# MCU.net
KiCad netlist of a schematic drawn in EasyEDA Pro
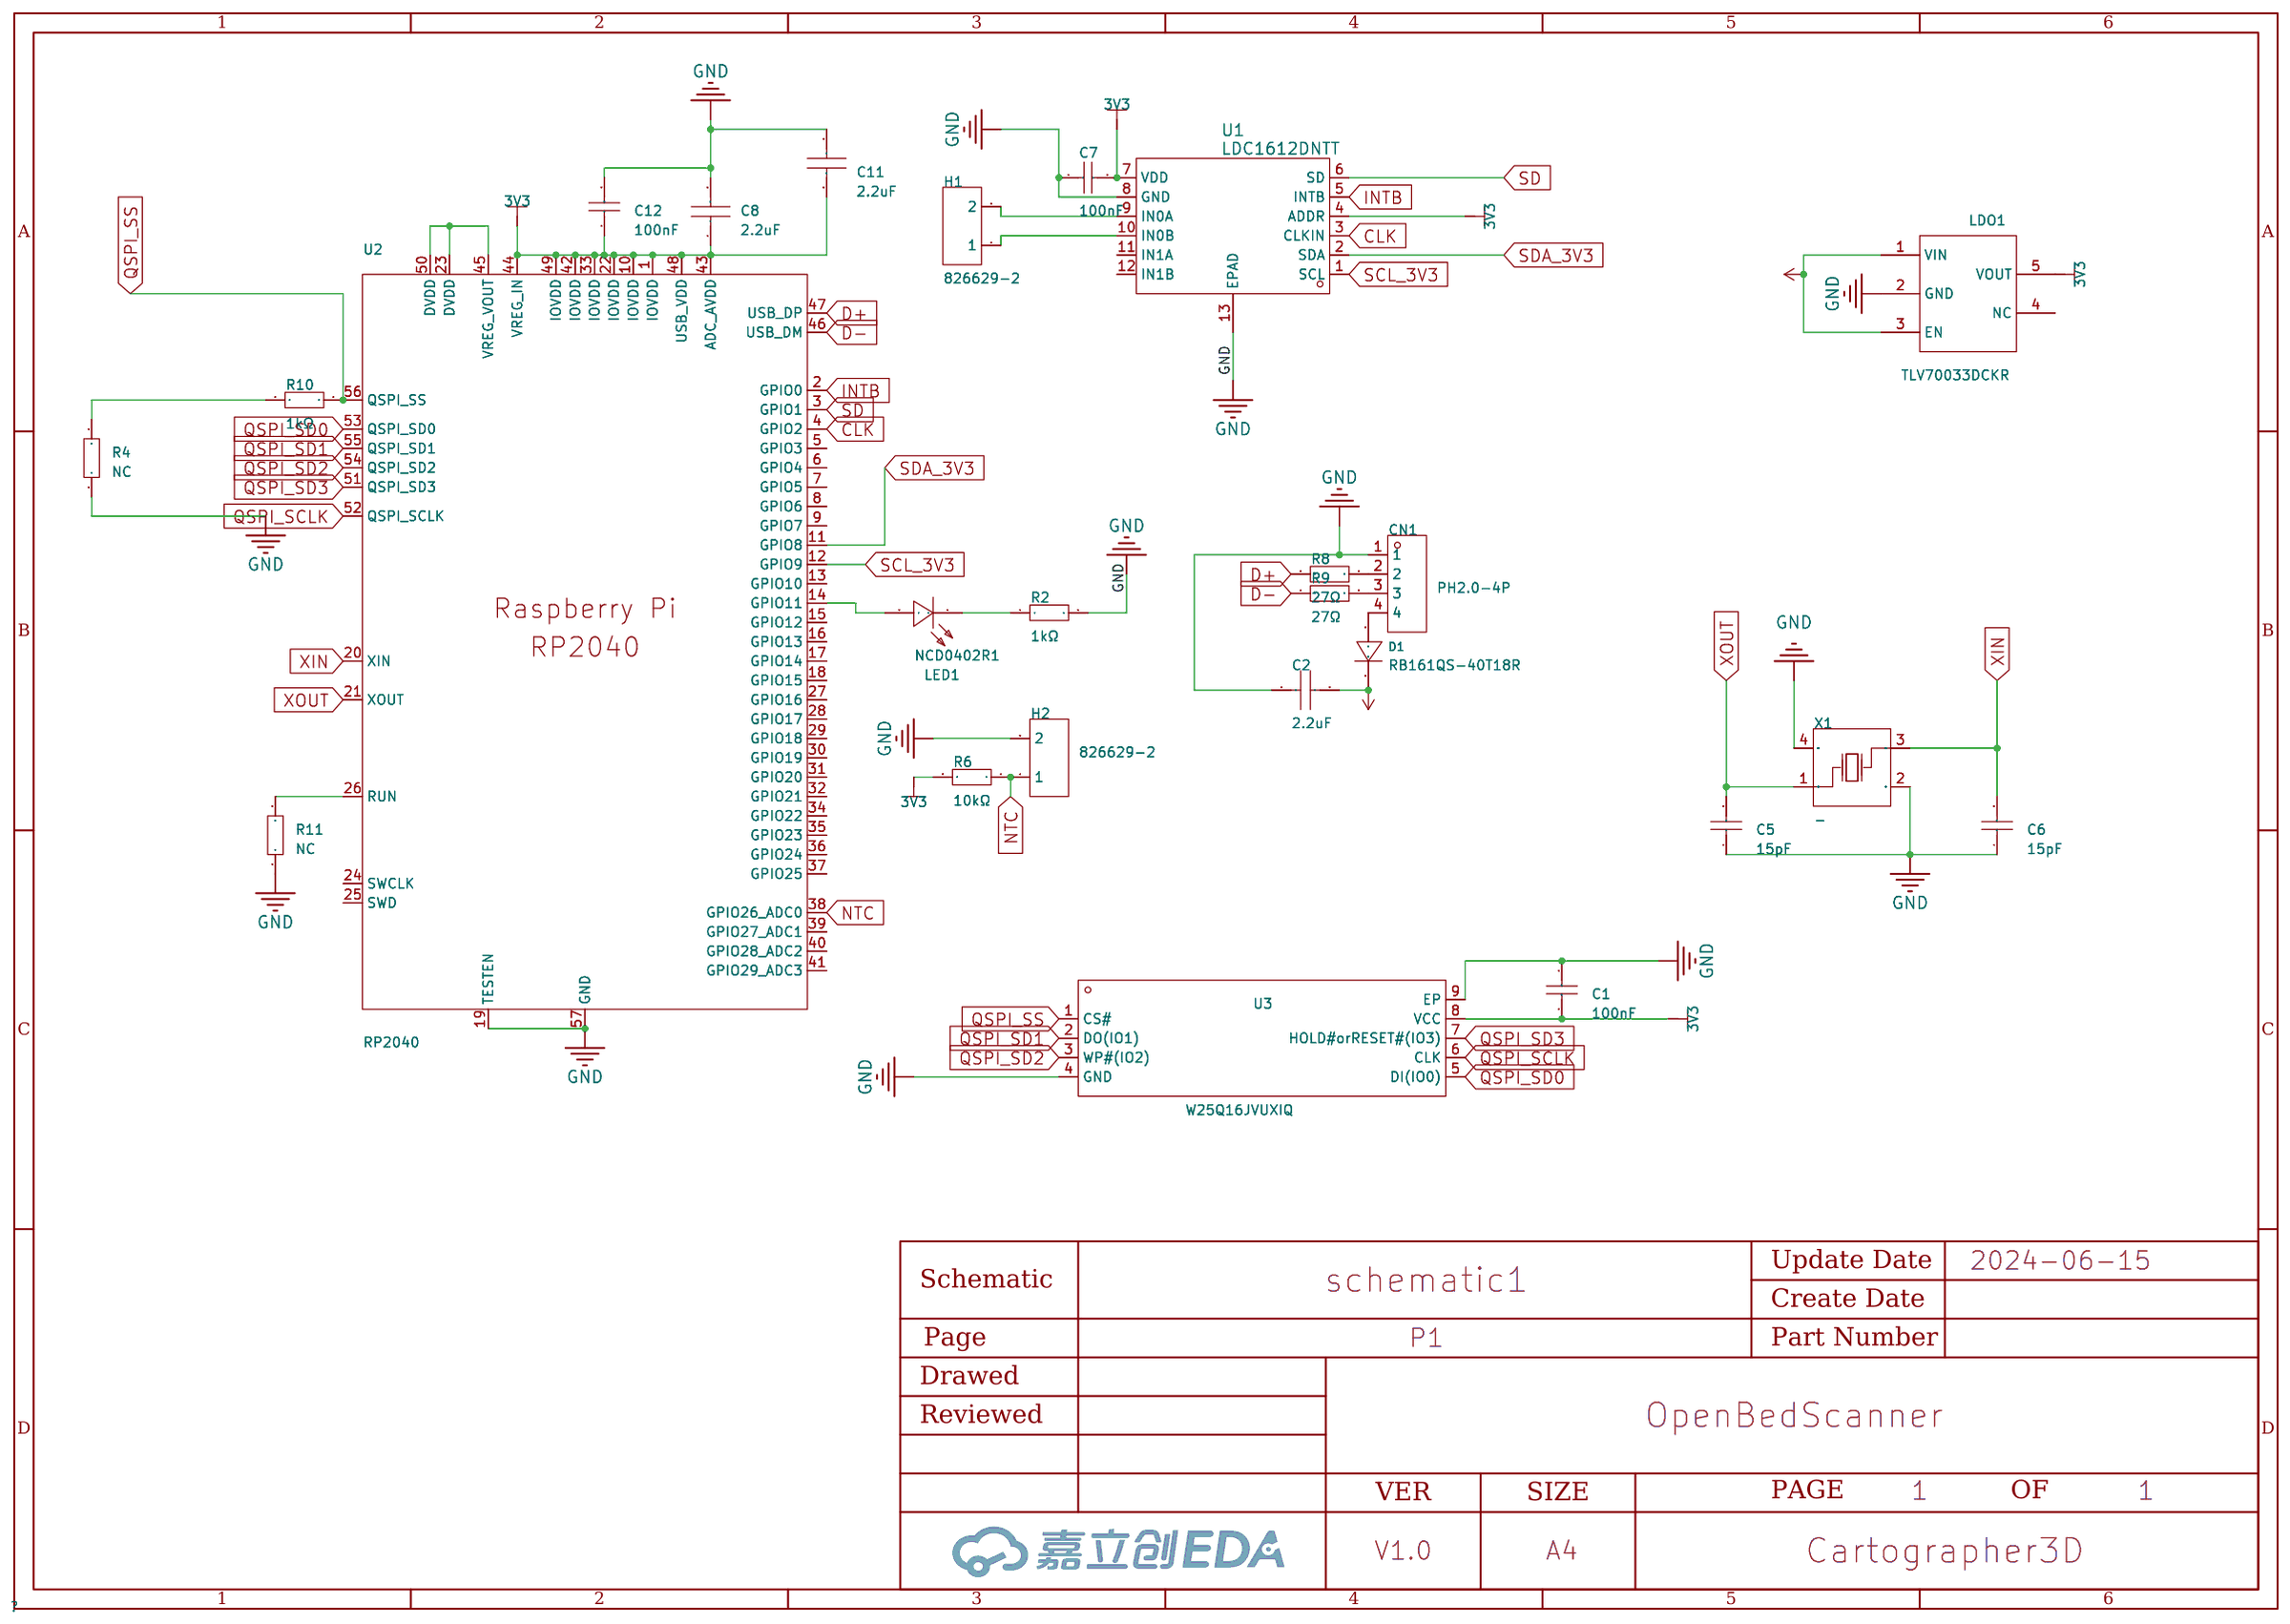
[diagram p0: schematic sheet]

(export (version "E")
  (design (tool "Eeschema 10.0.6"))
  (components
    (comp (ref "C1")
      (value "100nF")
      (footprint "easyedapro:C0402")
      (description "容值:100nF;精度:±10%;额定电压:16V;材质(温度系数):X7R;")
      (fields (field (name "Manufacturer Part") "0402B104K160NT") (field (name "Manufacturer") "FH(风华)"))
      (libsource (lib "easyedapro") (part "0402B104K160NT"))
    )
    (comp (ref "C2")
      (value "2.2uF")
      (footprint "easyedapro:C0402")
      (description "容值:2.2uF;精度:±20%;额定电压:6.3V;材质(温度系数):X5R;")
      (fields
        (field (name "Manufacturer Part") "CL05A225MQ5NSNC")
        (field (name "Manufacturer") "SAMSUNG(三星)")
      )
      (libsource (lib "easyedapro") (part "CL05A225MQ5NSNC"))
    )
    (comp (ref "C5")
      (value "15pF")
      (footprint "easyedapro:C0402")
      (description "容值:15pF;精度:±5%;额定电压:50V;材质(温度系数):C0G;")
      (fields (field (name "Manufacturer Part") "0402CG150J500NT") (field (name "Manufacturer") "FH(风华)"))
      (libsource (lib "easyedapro") (part "0402CG150J500NT"))
    )
    (comp (ref "C6")
      (value "15pF")
      (footprint "easyedapro:C0402")
      (description "容值:15pF;精度:±5%;额定电压:50V;材质(温度系数):C0G;")
      (fields (field (name "Manufacturer Part") "0402CG150J500NT") (field (name "Manufacturer") "FH(风华)"))
      (libsource (lib "easyedapro") (part "0402CG150J500NT"))
    )
    (comp (ref "C7")
      (value "100nF")
      (footprint "easyedapro:C0603")
      (description "容值:100nF;精度:±10%;额定电压:50V;材质(温度系数):X7R;")
      (fields (field (name "Manufacturer Part") "0402B104K160NT") (field (name "Manufacturer") "FH(风华)"))
      (libsource (lib "easyedapro") (part "0603B104K500NT"))
    )
    (comp (ref "C8")
      (value "2.2uF")
      (footprint "easyedapro:C0402")
      (description "容值:2.2uF;精度:±20%;额定电压:6.3V;材质(温度系数):X5R;")
      (fields
        (field (name "Manufacturer Part") "CL05A225MQ5NSNC")
        (field (name "Manufacturer") "SAMSUNG(三星)")
      )
      (libsource (lib "easyedapro") (part "CL05A225MQ5NSNC"))
    )
    (comp (ref "C11")
      (value "2.2uF")
      (footprint "easyedapro:C0402")
      (description "容值:2.2uF;精度:±20%;额定电压:6.3V;材质(温度系数):X5R;")
      (fields
        (field (name "Manufacturer Part") "CL05A225MQ5NSNC")
        (field (name "Manufacturer") "SAMSUNG(三星)")
      )
      (libsource (lib "easyedapro") (part "CL05A225MQ5NSNC"))
    )
    (comp (ref "C12")
      (value "100nF")
      (footprint "easyedapro:C0603")
      (description "容值:100nF;精度:±10%;额定电压:50V;材质(温度系数):X7R;")
      (fields (field (name "Manufacturer Part") "0402B104K160NT") (field (name "Manufacturer") "FH(风华)"))
      (libsource (lib "easyedapro") (part "0603B104K500NT"))
    )
    (comp (ref "CN1")
      (value "PH2.0-4P")
      (footprint "easyedapro:CONN-TH_PH2.0-4P")
      (fields (field (name "Manufacturer") "CAX(创都)"))
      (libsource (lib "easyedapro") (part "PH2.0-4P"))
    )
    (comp (ref "D1")
      (value "RB161QS-40T18R")
      (footprint "easyedapro:X2-DFN1006-2_L1.0-W0.6-P0.65-RD")
      (fields (field (name "Manufacturer") "ROHM(罗姆)"))
      (libsource (lib "easyedapro") (part "RB161QS-40T18R"))
    )
    (comp (ref "H1")
      (value "826629-2")
      (footprint "easyedapro:HDR-TH_2P-P2.54-V-M-1")
      (fields (field (name "Manufacturer") "TE Connectivity(美国泰科)"))
      (libsource (lib "easyedapro") (part "Header-Male-2.54_1x2"))
    )
    (comp (ref "H2")
      (value "826629-2")
      (footprint "easyedapro:HDR-TH_2P-P2.54-V-M-1")
      (fields (field (name "Manufacturer") "TE Connectivity(美国泰科)"))
      (libsource (lib "easyedapro") (part "Header-Male-2.54_1x2"))
    )
    (comp (ref "LDO1")
      (value "TLV70033DCKR")
      (footprint "easyedapro:SOT-23-5_L3.0-W1.7-P0.95-LS2.8-BL")
      (description "输出类型:固定;输出极性:正;最大输入电压:5.5V;输出电压:3.3V;输出电流:500mA;电源纹波抑制比(PSRR):50dB@(10kHz);")
      (fields (field (name "Manufacturer") "TI(德州仪器)"))
      (libsource (lib "easyedapro") (part "RT9013-33GB"))
    )
    (comp (ref "LED1")
      (value "NCD0402R1")
      (footprint "easyedapro:LED0402-RD")
      (description "发光颜色:红灯;")
      (fields (field (name "Manufacturer") "国星光电"))
      (libsource (lib "easyedapro") (part "FC-F1005HRK-620H5"))
    )
    (comp (ref "R2")
      (value "1kΩ")
      (footprint "easyedapro:R0402")
      (description "电阻类型:厚膜电阻;阻值:10kΩ;精度:±1%;功率:62.5mW;")
      (fields
        (field (name "Manufacturer Part") "0402WGF1001TCE")
        (field (name "Manufacturer") "UNI-ROYAL(厚声)")
      )
      (libsource (lib "easyedapro") (part "0402WGF1002TCE"))
    )
    (comp (ref "R4")
      (value "NC")
      (footprint "easyedapro:R0805")
      (description "电阻类型:厚膜电阻;阻值:10kΩ;精度:±1%;功率:125mW;")
      (fields
        (field (name "Manufacturer Part") "0805W8F1002T5E")
        (field (name "Manufacturer") "UNI-ROYAL(厚声)")
      )
      (libsource (lib "easyedapro") (part "0805W8F1002T5E"))
    )
    (comp (ref "R6")
      (value "10kΩ")
      (footprint "easyedapro:R0402")
      (description "电阻类型:厚膜电阻;阻值:1kΩ;精度:±1%;功率:62.5mW;")
      (fields
        (field (name "Manufacturer Part") "0402WGF1002TCE")
        (field (name "Manufacturer") "UNI-ROYAL(厚声)")
      )
      (libsource (lib "easyedapro") (part "0402WGF1001TCE"))
    )
    (comp (ref "R8")
      (value "27Ω")
      (footprint "easyedapro:R0402")
      (description "电阻类型:厚膜电阻;阻值:27Ω;精度:±1%;功率:62.5mW;")
      (fields
        (field (name "Manufacturer Part") "0402WGF270JTCE")
        (field (name "Manufacturer") "UNI-ROYAL(厚声)")
      )
      (libsource (lib "easyedapro") (part "0402WGF270JTCE"))
    )
    (comp (ref "R9")
      (value "27Ω")
      (footprint "easyedapro:R0402")
      (description "电阻类型:厚膜电阻;阻值:27Ω;精度:±1%;功率:62.5mW;")
      (fields
        (field (name "Manufacturer Part") "0402WGF270JTCE")
        (field (name "Manufacturer") "UNI-ROYAL(厚声)")
      )
      (libsource (lib "easyedapro") (part "0402WGF270JTCE"))
    )
    (comp (ref "R10")
      (value "1kΩ")
      (footprint "easyedapro:R0402")
      (description "电阻类型:厚膜电阻;阻值:10kΩ;精度:±1%;功率:62.5mW;")
      (fields
        (field (name "Manufacturer Part") "0402WGF1001TCE")
        (field (name "Manufacturer") "UNI-ROYAL(厚声)")
      )
      (libsource (lib "easyedapro") (part "0402WGF1002TCE"))
    )
    (comp (ref "R11")
      (value "NC")
      (footprint "easyedapro:R0805")
      (description "电阻类型:厚膜电阻;阻值:10kΩ;精度:±1%;功率:125mW;")
      (fields
        (field (name "Manufacturer Part") "0805W8F1002T5E")
        (field (name "Manufacturer") "UNI-ROYAL(厚声)")
      )
      (libsource (lib "easyedapro") (part "0805W8F1002T5E"))
    )
    (comp (ref "U1")
      (value "LDC1612DNTT")
      (footprint "easyedapro:WSON-12_L4.0-W4.0-P0.50-BL-EP")
      (fields (field (name "Manufacturer") "TI(德州仪器)"))
      (libsource (lib "easyedapro") (part "LDC1612DNTT"))
    )
    (comp (ref "U2")
      (value "RP2040")
      (footprint "easyedapro:LQFN-56_L7.0-W7.0-P0.4-EP")
      (description "应用领域:-;CPU内核:ARM-M系列;CPU最大主频:133MHz;工作电压范围:-;程序存储容量:-;程序存储器类型:-;RAM总容量:264KB;GPIO端口数量:30;")
      (fields (field (name "Manufacturer") "Raspberry Pi(树莓派)"))
      (libsource (lib "easyedapro") (part "RP2040"))
    )
    (comp (ref "U3")
      (value "W25Q16JVUXIQ")
      (footprint "easyedapro:USON-8_L3.0-W2.0-P0.50-BL-EP")
      (description "128Mbit(16MBx8bit),高速版,133MHz(266/532MHz Dual/Quad-SPI,66MB/S),比W25Q128FVSIG,W25Q128FVFIG更高速")
      (fields (field (name "Manufacturer") "WINBOND(华邦)"))
      (libsource (lib "easyedapro") (part "W25Q16JVUXIQ"))
    )
    (comp (ref "X1")
      (value "-")
      (footprint "easyedapro:OSC-SMD_4P-L3.2-W2.5-BL")
      (description "频率:12MHz;频率公差:±10ppm;负载电容:9pF;")
      (fields
        (field (name "Manufacturer Part") "XYDBPCNANF-12MHZ")
        (field (name "Manufacturer") "TAITIEN(泰艺电子)")
      )
      (libsource (lib "easyedapro") (part "X322512MLB4SI"))
    )
  )
  (nets
    (net (code "1") (name "3V3") (class "Default")
      (node (ref "C1") (pin "1") (pinfunction "1_1") (pintype "input"))
      (node (ref "C11") (pin "2") (pinfunction "2_2") (pintype "input"))
      (node (ref "C12") (pin "1") (pinfunction "1_1") (pintype "input"))
      (node (ref "C7") (pin "2") (pinfunction "2_2") (pintype "input"))
      (node (ref "C8") (pin "1") (pinfunction "1_1") (pintype "input"))
      (node (ref "LDO1") (pin "5") (pinfunction "VOUT_5") (pintype "input"))
      (node (ref "R6") (pin "2") (pinfunction "2_2") (pintype "input"))
      (node (ref "U1") (pin "4") (pinfunction "ADDR_4") (pintype "input"))
      (node (ref "U1") (pin "7") (pinfunction "VDD_7") (pintype "input"))
      (node (ref "U2") (pin "1") (pinfunction "IOVDD_1") (pintype "bidirectional"))
      (node (ref "U2") (pin "10") (pinfunction "IOVDD_10") (pintype "bidirectional"))
      (node (ref "U2") (pin "22") (pinfunction "IOVDD_22") (pintype "bidirectional"))
      (node (ref "U2") (pin "33") (pinfunction "IOVDD_33") (pintype "bidirectional"))
      (node (ref "U2") (pin "42") (pinfunction "IOVDD_42") (pintype "bidirectional"))
      (node (ref "U2") (pin "43") (pinfunction "ADC_AVDD_43") (pintype "bidirectional"))
      (node (ref "U2") (pin "44") (pinfunction "VREG_IN_44") (pintype "bidirectional"))
      (node (ref "U2") (pin "48") (pinfunction "USB_VDD_48") (pintype "bidirectional"))
      (node (ref "U2") (pin "49") (pinfunction "IOVDD_49") (pintype "bidirectional"))
      (node (ref "U3") (pin "8") (pinfunction "VCC_8") (pintype "input"))
    )
    (net (code "2") (name "5V") (class "Default")
      (node (ref "C2") (pin "2") (pinfunction "2_2") (pintype "input"))
      (node (ref "D1") (pin "1") (pinfunction "C_1") (pintype "input"))
      (node (ref "LDO1") (pin "1") (pinfunction "VIN_1") (pintype "input"))
      (node (ref "LDO1") (pin "3") (pinfunction "EN_3") (pintype "input"))
    )
    (net (code "3") (name "CLK") (class "Default")
      (node (ref "U1") (pin "3") (pinfunction "CLKIN_3") (pintype "input"))
      (node (ref "U2") (pin "4") (pinfunction "GPIO2_4") (pintype "bidirectional"))
    )
    (net (code "4") (name "D+") (class "Default")
      (node (ref "R8") (pin "1") (pinfunction "1_1") (pintype "input"))
      (node (ref "U2") (pin "47") (pinfunction "USB_DP_47") (pintype "bidirectional"))
    )
    (net (code "5") (name "D-") (class "Default")
      (node (ref "R9") (pin "1") (pinfunction "1_1") (pintype "input"))
      (node (ref "U2") (pin "46") (pinfunction "USB_DM_46") (pintype "bidirectional"))
    )
    (net (code "6") (name "GND") (class "Default")
      (node (ref "C1") (pin "2") (pinfunction "2_2") (pintype "input"))
      (node (ref "C11") (pin "1") (pinfunction "1_1") (pintype "input"))
      (node (ref "C12") (pin "2") (pinfunction "2_2") (pintype "input"))
      (node (ref "C2") (pin "1") (pinfunction "1_1") (pintype "input"))
      (node (ref "C5") (pin "1") (pinfunction "1_1") (pintype "input"))
      (node (ref "C6") (pin "1") (pinfunction "1_1") (pintype "input"))
      (node (ref "C7") (pin "1") (pinfunction "1_1") (pintype "input"))
      (node (ref "C8") (pin "2") (pinfunction "2_2") (pintype "input"))
      (node (ref "CN1") (pin "1") (pinfunction "1_1") (pintype "input"))
      (node (ref "H2") (pin "2") (pinfunction "2_2") (pintype "input"))
      (node (ref "LDO1") (pin "2") (pinfunction "GND_2") (pintype "input"))
      (node (ref "R11") (pin "1") (pinfunction "1_1") (pintype "input"))
      (node (ref "R2") (pin "2") (pinfunction "2_2") (pintype "input"))
      (node (ref "R4") (pin "2") (pinfunction "2_2") (pintype "input"))
      (node (ref "U1") (pin "13") (pinfunction "EPAD_13") (pintype "input"))
      (node (ref "U1") (pin "8") (pinfunction "GND_8") (pintype "input"))
      (node (ref "U2") (pin "19") (pinfunction "TESTEN_19") (pintype "input"))
      (node (ref "U2") (pin "57") (pinfunction "GND_57") (pintype "bidirectional"))
      (node (ref "U3") (pin "4") (pinfunction "GND_4") (pintype "input"))
      (node (ref "U3") (pin "9") (pinfunction "EP_9") (pintype "input"))
      (node (ref "X1") (pin "2") (pinfunction "GND_2") (pintype "input"))
      (node (ref "X1") (pin "4") (pinfunction "GND_4") (pintype "input"))
    )
    (net (code "7") (name "INTB") (class "Default")
      (node (ref "U1") (pin "5") (pinfunction "INTB_5") (pintype "input"))
      (node (ref "U2") (pin "2") (pinfunction "GPIO0_2") (pintype "bidirectional"))
    )
    (net (code "8") (name "NTC") (class "Default")
      (node (ref "H2") (pin "1") (pinfunction "1_1") (pintype "input"))
      (node (ref "R6") (pin "1") (pinfunction "1_1") (pintype "input"))
      (node (ref "U2") (pin "38") (pinfunction "GPIO26_ADC0_38") (pintype "bidirectional"))
    )
    (net (code "9") (name "Net-(CN1-Pad2)") (class "Default")
      (node (ref "CN1") (pin "2") (pinfunction "2_2") (pintype "input"))
      (node (ref "R8") (pin "2") (pinfunction "2_2") (pintype "input"))
    )
    (net (code "10") (name "Net-(CN1-Pad3)") (class "Default")
      (node (ref "CN1") (pin "3") (pinfunction "3_3") (pintype "input"))
      (node (ref "R9") (pin "2") (pinfunction "2_2") (pintype "input"))
    )
    (net (code "11") (name "Net-(D1-A)") (class "Default")
      (node (ref "CN1") (pin "4") (pinfunction "4_4") (pintype "input"))
      (node (ref "D1") (pin "2") (pinfunction "A_2") (pintype "input"))
    )
    (net (code "12") (name "Net-(LED1-A)") (class "Default")
      (node (ref "LED1") (pin "2") (pinfunction "A_2") (pintype "input"))
      (node (ref "U2") (pin "14") (pinfunction "GPIO11_14") (pintype "bidirectional"))
    )
    (net (code "13") (name "Net-(LED1-K)") (class "Default")
      (node (ref "LED1") (pin "1") (pinfunction "K_1") (pintype "input"))
      (node (ref "R2") (pin "1") (pinfunction "1_1") (pintype "input"))
    )
    (net (code "14") (name "Net-(R10-Pad2)") (class "Default")
      (node (ref "R10") (pin "2") (pinfunction "2_2") (pintype "input"))
      (node (ref "R4") (pin "1") (pinfunction "1_1") (pintype "input"))
    )
    (net (code "15") (name "Net-(U1-IN0A)") (class "Default")
      (node (ref "H1") (pin "2") (pinfunction "2_2") (pintype "input"))
      (node (ref "U1") (pin "9") (pinfunction "IN0A_9") (pintype "input"))
    )
    (net (code "16") (name "Net-(U1-IN0B)") (class "Default")
      (node (ref "H1") (pin "1") (pinfunction "1_1") (pintype "input"))
      (node (ref "U1") (pin "10") (pinfunction "IN0B_10") (pintype "input"))
    )
    (net (code "17") (name "Net-(U2-RUN)") (class "Default")
      (node (ref "R11") (pin "2") (pinfunction "2_2") (pintype "input"))
      (node (ref "U2") (pin "26") (pinfunction "RUN_26") (pintype "input"))
    )
    (net (code "18") (name "Net-(U2-VREG_VOUT)") (class "Default")
      (node (ref "U2") (pin "23") (pinfunction "DVDD_23") (pintype "bidirectional"))
      (node (ref "U2") (pin "45") (pinfunction "VREG_VOUT_45") (pintype "bidirectional"))
      (node (ref "U2") (pin "50") (pinfunction "DVDD_50") (pintype "bidirectional"))
    )
    (net (code "19") (name "QSPI_SCLK") (class "Default")
      (node (ref "U2") (pin "52") (pinfunction "QSPI_SCLK_52") (pintype "output"))
      (node (ref "U3") (pin "6") (pinfunction "CLK_6") (pintype "input"))
    )
    (net (code "20") (name "QSPI_SD0") (class "Default")
      (node (ref "U2") (pin "53") (pinfunction "QSPI_SD0_53") (pintype "bidirectional"))
      (node (ref "U3") (pin "5") (pinfunction "DI(IO0)_5") (pintype "input"))
    )
    (net (code "21") (name "QSPI_SD1") (class "Default")
      (node (ref "U2") (pin "55") (pinfunction "QSPI_SD1_55") (pintype "bidirectional"))
      (node (ref "U3") (pin "2") (pinfunction "DO(IO1)_2") (pintype "input"))
    )
    (net (code "22") (name "QSPI_SD2") (class "Default")
      (node (ref "U2") (pin "54") (pinfunction "QSPI_SD2_54") (pintype "bidirectional"))
      (node (ref "U3") (pin "3") (pinfunction "WP#(IO2)_3") (pintype "input"))
    )
    (net (code "23") (name "QSPI_SD3") (class "Default")
      (node (ref "U2") (pin "51") (pinfunction "QSPI_SD3_51") (pintype "bidirectional"))
      (node (ref "U3") (pin "7") (pinfunction "HOLD#orRESET#(IO3)_7") (pintype "input"))
    )
    (net (code "24") (name "QSPI_SS") (class "Default")
      (node (ref "R10") (pin "1") (pinfunction "1_1") (pintype "input"))
      (node (ref "U2") (pin "56") (pinfunction "QSPI_SS_56") (pintype "bidirectional"))
      (node (ref "U3") (pin "1") (pinfunction "CS#_1") (pintype "input"))
    )
    (net (code "25") (name "SCL_3V3") (class "Default")
      (node (ref "U1") (pin "1") (pinfunction "SCL_1") (pintype "input"))
      (node (ref "U2") (pin "12") (pinfunction "GPIO9_12") (pintype "bidirectional"))
    )
    (net (code "26") (name "SD") (class "Default")
      (node (ref "U1") (pin "6") (pinfunction "SD_6") (pintype "input"))
      (node (ref "U2") (pin "3") (pinfunction "GPIO1_3") (pintype "bidirectional"))
    )
    (net (code "27") (name "SDA_3V3") (class "Default")
      (node (ref "U1") (pin "2") (pinfunction "SDA_2") (pintype "input"))
      (node (ref "U2") (pin "11") (pinfunction "GPIO8_11") (pintype "bidirectional"))
    )
    (net (code "28") (name "XIN") (class "Default")
      (node (ref "C6") (pin "2") (pinfunction "2_2") (pintype "input"))
      (node (ref "U2") (pin "20") (pinfunction "XIN_20") (pintype "input"))
      (node (ref "X1") (pin "3") (pinfunction "OSC2_3") (pintype "input"))
    )
    (net (code "29") (name "XOUT") (class "Default")
      (node (ref "C5") (pin "2") (pinfunction "2_2") (pintype "input"))
      (node (ref "U2") (pin "21") (pinfunction "XOUT_21") (pintype "input"))
      (node (ref "X1") (pin "1") (pinfunction "OSC1_1") (pintype "input"))
    )
    (net (code "30") (name "unconnected-(LDO1-NC-Pad4)") (class "Default")
      (node (ref "LDO1") (pin "4") (pinfunction "NC_4") (pintype "input"))
    )
    (net (code "31") (name "unconnected-(U1-IN1A-Pad11)") (class "Default")
      (node (ref "U1") (pin "11") (pinfunction "IN1A_11") (pintype "input"))
    )
    (net (code "32") (name "unconnected-(U1-IN1B-Pad12)") (class "Default")
      (node (ref "U1") (pin "12") (pinfunction "IN1B_12") (pintype "input"))
    )
    (net (code "33") (name "unconnected-(U2-GPIO3-Pad5)") (class "Default")
      (node (ref "U2") (pin "5") (pinfunction "GPIO3_5") (pintype "bidirectional"))
    )
    (net (code "34") (name "unconnected-(U2-GPIO4-Pad6)") (class "Default")
      (node (ref "U2") (pin "6") (pinfunction "GPIO4_6") (pintype "bidirectional"))
    )
    (net (code "35") (name "unconnected-(U2-GPIO5-Pad7)") (class "Default")
      (node (ref "U2") (pin "7") (pinfunction "GPIO5_7") (pintype "bidirectional"))
    )
    (net (code "36") (name "unconnected-(U2-GPIO6-Pad8)") (class "Default")
      (node (ref "U2") (pin "8") (pinfunction "GPIO6_8") (pintype "bidirectional"))
    )
    (net (code "37") (name "unconnected-(U2-GPIO7-Pad9)") (class "Default")
      (node (ref "U2") (pin "9") (pinfunction "GPIO7_9") (pintype "bidirectional"))
    )
    (net (code "38") (name "unconnected-(U2-GPIO10-Pad13)") (class "Default")
      (node (ref "U2") (pin "13") (pinfunction "GPIO10_13") (pintype "bidirectional"))
    )
    (net (code "39") (name "unconnected-(U2-GPIO12-Pad15)") (class "Default")
      (node (ref "U2") (pin "15") (pinfunction "GPIO12_15") (pintype "bidirectional"))
    )
    (net (code "40") (name "unconnected-(U2-GPIO13-Pad16)") (class "Default")
      (node (ref "U2") (pin "16") (pinfunction "GPIO13_16") (pintype "bidirectional"))
    )
    (net (code "41") (name "unconnected-(U2-GPIO14-Pad17)") (class "Default")
      (node (ref "U2") (pin "17") (pinfunction "GPIO14_17") (pintype "bidirectional"))
    )
    (net (code "42") (name "unconnected-(U2-GPIO15-Pad18)") (class "Default")
      (node (ref "U2") (pin "18") (pinfunction "GPIO15_18") (pintype "bidirectional"))
    )
    (net (code "43") (name "unconnected-(U2-GPIO16-Pad27)") (class "Default")
      (node (ref "U2") (pin "27") (pinfunction "GPIO16_27") (pintype "bidirectional"))
    )
    (net (code "44") (name "unconnected-(U2-GPIO17-Pad28)") (class "Default")
      (node (ref "U2") (pin "28") (pinfunction "GPIO17_28") (pintype "bidirectional"))
    )
    (net (code "45") (name "unconnected-(U2-GPIO18-Pad29)") (class "Default")
      (node (ref "U2") (pin "29") (pinfunction "GPIO18_29") (pintype "bidirectional"))
    )
    (net (code "46") (name "unconnected-(U2-GPIO19-Pad30)") (class "Default")
      (node (ref "U2") (pin "30") (pinfunction "GPIO19_30") (pintype "bidirectional"))
    )
    (net (code "47") (name "unconnected-(U2-GPIO20-Pad31)") (class "Default")
      (node (ref "U2") (pin "31") (pinfunction "GPIO20_31") (pintype "bidirectional"))
    )
    (net (code "48") (name "unconnected-(U2-GPIO21-Pad32)") (class "Default")
      (node (ref "U2") (pin "32") (pinfunction "GPIO21_32") (pintype "bidirectional"))
    )
    (net (code "49") (name "unconnected-(U2-GPIO22-Pad34)") (class "Default")
      (node (ref "U2") (pin "34") (pinfunction "GPIO22_34") (pintype "bidirectional"))
    )
    (net (code "50") (name "unconnected-(U2-GPIO23-Pad35)") (class "Default")
      (node (ref "U2") (pin "35") (pinfunction "GPIO23_35") (pintype "bidirectional"))
    )
    (net (code "51") (name "unconnected-(U2-GPIO24-Pad36)") (class "Default")
      (node (ref "U2") (pin "36") (pinfunction "GPIO24_36") (pintype "bidirectional"))
    )
    (net (code "52") (name "unconnected-(U2-GPIO25-Pad37)") (class "Default")
      (node (ref "U2") (pin "37") (pinfunction "GPIO25_37") (pintype "bidirectional"))
    )
    (net (code "53") (name "unconnected-(U2-GPIO27_ADC1-Pad39)") (class "Default")
      (node (ref "U2") (pin "39") (pinfunction "GPIO27_ADC1_39") (pintype "bidirectional"))
    )
    (net (code "54") (name "unconnected-(U2-GPIO28_ADC2-Pad40)") (class "Default")
      (node (ref "U2") (pin "40") (pinfunction "GPIO28_ADC2_40") (pintype "bidirectional"))
    )
    (net (code "55") (name "unconnected-(U2-GPIO29_ADC3-Pad41)") (class "Default")
      (node (ref "U2") (pin "41") (pinfunction "GPIO29_ADC3_41") (pintype "bidirectional"))
    )
    (net (code "56") (name "unconnected-(U2-SWCLK-Pad24)") (class "Default")
      (node (ref "U2") (pin "24") (pinfunction "SWCLK_24") (pintype "output"))
    )
    (net (code "57") (name "unconnected-(U2-SWD-Pad25)") (class "Default")
      (node (ref "U2") (pin "25") (pinfunction "SWD_25") (pintype "bidirectional"))
    )
  )
)
